# Peripherals.net
KiCad netlist of a schematic drawn in Altium Designer
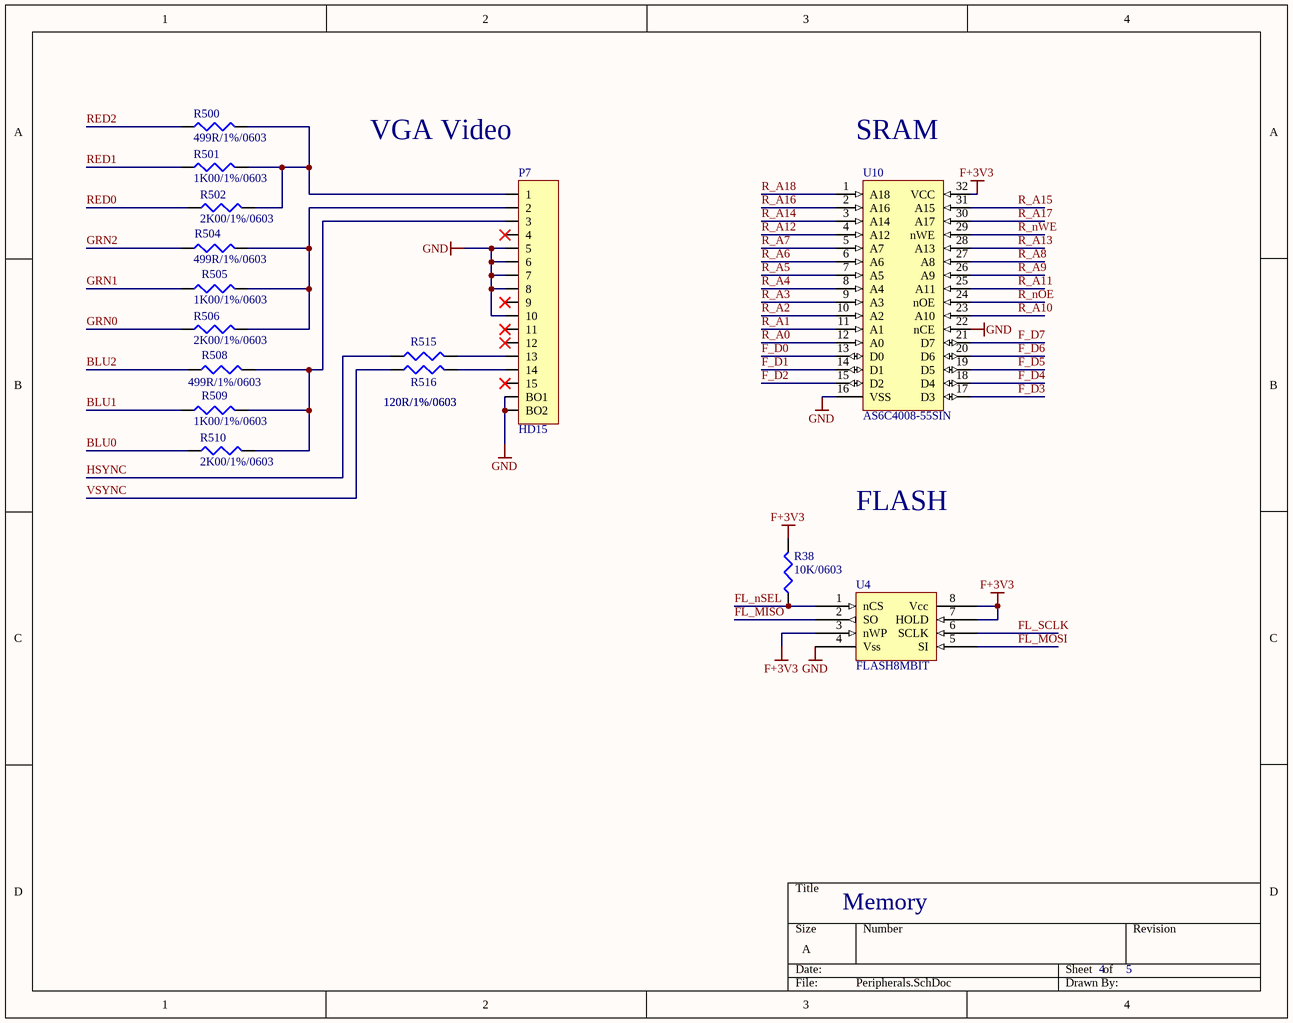
[diagram p0: Peripherals.SchDoc]

(export (version "E")
  (design (tool "Eeschema 10.0.6"))
  (components
    (comp (ref "P7")
      (value "HD15")
      (footprint "DB15FLC")
      (description "CONN DSUB HD RCPT 15POS R/A SLDR")
      (libsource (lib "C64Interface") (part "HD15"))
    )
    (comp (ref "R38")
      (value "10K/0603")
      (footprint "0603")
      (description "RES 10.0K OHM 1/10W 1% 0603 SMD")
      (fields (field (name "MFG") "Dale/Vishay"))
      (libsource (lib "C64Interface") (part "10K/0603"))
    )
    (comp (ref "R500")
      (value "499R/1%/0603")
      (footprint "0603")
      (description "499 Ohms ±1% 0.1W, 1/10W Chip Resistor 0603 (1608 Metric) Moisture Resistant Thick Film")
      (fields (field (name "MFG") "Yeago"))
      (libsource (lib "Resistors") (part "499R/1%/0603"))
    )
    (comp (ref "R501")
      (value "1K00/1%/0603")
      (footprint "0603")
      (description "1 kOhms ±1% 0.1W, 1/10W Chip Resistor 0603 (1608 Metric) Moisture Resistant Thick Film")
      (fields (field (name "MFG") "Yeago"))
      (libsource (lib "Resistors") (part "1K00/1%/0603"))
    )
    (comp (ref "R502")
      (value "2K00/1%/0603")
      (footprint "0603")
      (description "2 kOhms ±1% 0.1W, 1/10W Chip Resistor 0603 (1608 Metric) Moisture Resistant Thick Film")
      (fields (field (name "MFG") "Yeago"))
      (libsource (lib "Resistors") (part "2K00/1%/0603"))
    )
    (comp (ref "R504")
      (value "499R/1%/0603")
      (footprint "0603")
      (description "499 Ohms ±1% 0.1W, 1/10W Chip Resistor 0603 (1608 Metric) Moisture Resistant Thick Film")
      (fields (field (name "MFG") "Yeago"))
      (libsource (lib "Resistors") (part "499R/1%/0603"))
    )
    (comp (ref "R505")
      (value "1K00/1%/0603")
      (footprint "0603")
      (description "1 kOhms ±1% 0.1W, 1/10W Chip Resistor 0603 (1608 Metric) Moisture Resistant Thick Film")
      (fields (field (name "MFG") "Yeago"))
      (libsource (lib "Resistors") (part "1K00/1%/0603"))
    )
    (comp (ref "R506")
      (value "2K00/1%/0603")
      (footprint "0603")
      (description "2 kOhms ±1% 0.1W, 1/10W Chip Resistor 0603 (1608 Metric) Moisture Resistant Thick Film")
      (fields (field (name "MFG") "Yeago"))
      (libsource (lib "Resistors") (part "2K00/1%/0603"))
    )
    (comp (ref "R508")
      (value "499R/1%/0603")
      (footprint "0603")
      (description "499 Ohms ±1% 0.1W, 1/10W Chip Resistor 0603 (1608 Metric) Moisture Resistant Thick Film")
      (fields (field (name "MFG") "Yeago"))
      (libsource (lib "Resistors") (part "499R/1%/0603"))
    )
    (comp (ref "R509")
      (value "1K00/1%/0603")
      (footprint "0603")
      (description "1 kOhms ±1% 0.1W, 1/10W Chip Resistor 0603 (1608 Metric) Moisture Resistant Thick Film")
      (fields (field (name "MFG") "Yeago"))
      (libsource (lib "Resistors") (part "1K00/1%/0603"))
    )
    (comp (ref "R510")
      (value "2K00/1%/0603")
      (footprint "0603")
      (description "2 kOhms ±1% 0.1W, 1/10W Chip Resistor 0603 (1608 Metric) Moisture Resistant Thick Film")
      (fields (field (name "MFG") "Yeago"))
      (libsource (lib "Resistors") (part "2K00/1%/0603"))
    )
    (comp (ref "R515")
      (value "120R/1%/0603")
      (footprint "0603")
      (description "120 Ohms ±1% 0.1W, 1/10W Chip Resistor 0603 (1608 Metric) Moisture Resistant Thick Film")
      (fields (field (name "MFG") "Yaego"))
      (libsource (lib "C64Interface") (part "120R/1%/0603"))
    )
    (comp (ref "R516")
      (value "120R/1%/0603")
      (footprint "0603")
      (description "120 Ohms ±1% 0.1W, 1/10W Chip Resistor 0603 (1608 Metric) Moisture Resistant Thick Film")
      (fields (field (name "MFG") "Yaego"))
      (libsource (lib "C64Interface") (part "120R/1%/0603"))
    )
    (comp (ref "U4")
      (value "FLASH8MBIT")
      (footprint "SO-8WM")
      (description "IC FLASH 8MBIT SPI/QUAD 8SOIC")
      (fields (field (name "MFG") "Cyoress"))
      (libsource (lib "DigitalIC") (part "FLASH8MBIT"))
    )
    (comp (ref "U10")
      (value "AS6C4008-55SIN")
      (footprint "SOP32W")
      (description "SRAM - Asynchronous Memory IC 4Mb (512K x 8) Parallel 55 ns 32-SOP")
      (fields (field (name "MFG") "Alliance Memory, Inc."))
      (libsource (lib "DigitalIC") (part "AS6C4008-55SIN"))
    )
  )
  (nets
    (net (code "1") (name "/BLU0") (class "Default") (node (ref "R510") (pin "1") (pintype "passive")))
    (net (code "2") (name "/BLU1") (class "Default") (node (ref "R509") (pin "1") (pintype "passive")))
    (net (code "3") (name "/BLU2") (class "Default") (node (ref "R508") (pin "1") (pintype "passive")))
    (net (code "4") (name "/FL_MISO") (class "Default")
      (node (ref "U4") (pin "2") (pinfunction "SO_2") (pintype "output"))
    )
    (net (code "5") (name "/FL_MOSI") (class "Default")
      (node (ref "U4") (pin "5") (pinfunction "SI_5") (pintype "input"))
    )
    (net (code "6") (name "/FL_SCLK") (class "Default")
      (node (ref "U4") (pin "6") (pinfunction "SCLK_6") (pintype "input"))
    )
    (net (code "7") (name "/FL_nSEL") (class "Default")
      (node (ref "R38") (pin "1") (pintype "passive"))
      (node (ref "U4") (pin "1") (pinfunction "nCS_1") (pintype "input"))
    )
    (net (code "8") (name "/F_D0") (class "Default")
      (node (ref "U10") (pin "13") (pinfunction "D0_13") (pintype "bidirectional"))
    )
    (net (code "9") (name "/F_D1") (class "Default")
      (node (ref "U10") (pin "14") (pinfunction "D1_14") (pintype "bidirectional"))
    )
    (net (code "10") (name "/F_D2") (class "Default")
      (node (ref "U10") (pin "15") (pinfunction "D2_15") (pintype "bidirectional"))
    )
    (net (code "11") (name "/F_D3") (class "Default")
      (node (ref "U10") (pin "17") (pinfunction "D3_17") (pintype "bidirectional"))
    )
    (net (code "12") (name "/F_D4") (class "Default")
      (node (ref "U10") (pin "18") (pinfunction "D4_18") (pintype "bidirectional"))
    )
    (net (code "13") (name "/F_D5") (class "Default")
      (node (ref "U10") (pin "19") (pinfunction "D5_19") (pintype "bidirectional"))
    )
    (net (code "14") (name "/F_D6") (class "Default")
      (node (ref "U10") (pin "20") (pinfunction "D6_20") (pintype "bidirectional"))
    )
    (net (code "15") (name "/F_D7") (class "Default")
      (node (ref "U10") (pin "21") (pinfunction "D7_21") (pintype "bidirectional"))
    )
    (net (code "16") (name "/GRN0") (class "Default") (node (ref "R506") (pin "1") (pintype "passive")))
    (net (code "17") (name "/GRN1") (class "Default") (node (ref "R505") (pin "1") (pintype "passive")))
    (net (code "18") (name "/GRN2") (class "Default") (node (ref "R504") (pin "1") (pintype "passive")))
    (net (code "19") (name "/HSYNC") (class "Default") (node (ref "R515") (pin "1") (pintype "passive")))
    (net (code "20") (name "/RED0") (class "Default") (node (ref "R502") (pin "1") (pintype "passive")))
    (net (code "21") (name "/RED1") (class "Default") (node (ref "R501") (pin "1") (pintype "passive")))
    (net (code "22") (name "/RED2") (class "Default") (node (ref "R500") (pin "1") (pintype "passive")))
    (net (code "23") (name "/R_A0") (class "Default")
      (node (ref "U10") (pin "12") (pinfunction "A0_12") (pintype "input"))
    )
    (net (code "24") (name "/R_A1") (class "Default")
      (node (ref "U10") (pin "11") (pinfunction "A1_11") (pintype "input"))
    )
    (net (code "25") (name "/R_A2") (class "Default")
      (node (ref "U10") (pin "10") (pinfunction "A2_10") (pintype "input"))
    )
    (net (code "26") (name "/R_A3") (class "Default")
      (node (ref "U10") (pin "9") (pinfunction "A3_9") (pintype "input"))
    )
    (net (code "27") (name "/R_A4") (class "Default")
      (node (ref "U10") (pin "8") (pinfunction "A4_8") (pintype "input"))
    )
    (net (code "28") (name "/R_A5") (class "Default")
      (node (ref "U10") (pin "7") (pinfunction "A5_7") (pintype "input"))
    )
    (net (code "29") (name "/R_A6") (class "Default")
      (node (ref "U10") (pin "6") (pinfunction "A6_6") (pintype "input"))
    )
    (net (code "30") (name "/R_A7") (class "Default")
      (node (ref "U10") (pin "5") (pinfunction "A7_5") (pintype "input"))
    )
    (net (code "31") (name "/R_A8") (class "Default")
      (node (ref "U10") (pin "27") (pinfunction "A8_27") (pintype "input"))
    )
    (net (code "32") (name "/R_A9") (class "Default")
      (node (ref "U10") (pin "26") (pinfunction "A9_26") (pintype "input"))
    )
    (net (code "33") (name "/R_A10") (class "Default")
      (node (ref "U10") (pin "23") (pinfunction "A10_23") (pintype "input"))
    )
    (net (code "34") (name "/R_A11") (class "Default")
      (node (ref "U10") (pin "25") (pinfunction "A11_25") (pintype "input"))
    )
    (net (code "35") (name "/R_A12") (class "Default")
      (node (ref "U10") (pin "4") (pinfunction "A12_4") (pintype "input"))
    )
    (net (code "36") (name "/R_A13") (class "Default")
      (node (ref "U10") (pin "28") (pinfunction "A13_28") (pintype "input"))
    )
    (net (code "37") (name "/R_A14") (class "Default")
      (node (ref "U10") (pin "3") (pinfunction "A14_3") (pintype "input"))
    )
    (net (code "38") (name "/R_A15") (class "Default")
      (node (ref "U10") (pin "31") (pinfunction "A15_31") (pintype "input"))
    )
    (net (code "39") (name "/R_A16") (class "Default")
      (node (ref "U10") (pin "2") (pinfunction "A16_2") (pintype "input"))
    )
    (net (code "40") (name "/R_A17") (class "Default")
      (node (ref "U10") (pin "30") (pinfunction "A17_30") (pintype "input"))
    )
    (net (code "41") (name "/R_A18") (class "Default")
      (node (ref "U10") (pin "1") (pinfunction "A18_1") (pintype "input"))
    )
    (net (code "42") (name "/R_nOE") (class "Default")
      (node (ref "U10") (pin "24") (pinfunction "nOE_24") (pintype "input"))
    )
    (net (code "43") (name "/R_nWE") (class "Default")
      (node (ref "U10") (pin "29") (pinfunction "nWE_29") (pintype "input"))
    )
    (net (code "44") (name "/VSYNC") (class "Default") (node (ref "R516") (pin "1") (pintype "passive")))
    (net (code "45") (name "F+3V3") (class "Default")
      (node (ref "R38") (pin "2") (pintype "passive"))
      (node (ref "U10") (pin "32") (pinfunction "VCC_32") (pintype "input"))
      (node (ref "U4") (pin "3") (pinfunction "nWP_3") (pintype "input"))
      (node (ref "U4") (pin "7") (pinfunction "HOLD_7") (pintype "input"))
      (node (ref "U4") (pin "8") (pinfunction "Vcc_8") (pintype "power_in"))
    )
    (net (code "46") (name "GND") (class "Default")
      (node (ref "P7") (pin "10") (pinfunction "10_10") (pintype "passive"))
      (node (ref "P7") (pin "5") (pinfunction "5_5") (pintype "passive"))
      (node (ref "P7") (pin "6") (pinfunction "6_6") (pintype "passive"))
      (node (ref "P7") (pin "7") (pinfunction "7_7") (pintype "passive"))
      (node (ref "P7") (pin "8") (pinfunction "8_8") (pintype "passive"))
      (node (ref "P7") (pin "BO1") (pinfunction "BO1_BO1") (pintype "passive"))
      (node (ref "P7") (pin "BO2") (pinfunction "BO2_BO2") (pintype "passive"))
      (node (ref "U10") (pin "16") (pinfunction "VSS_16") (pintype "power_in"))
      (node (ref "U10") (pin "22") (pinfunction "nCE_22") (pintype "input"))
      (node (ref "U4") (pin "4") (pinfunction "Vss_4") (pintype "power_in"))
    )
    (net (code "47") (name "Net-(P7-Pad1)") (class "Default")
      (node (ref "P7") (pin "1") (pinfunction "1_1") (pintype "passive"))
      (node (ref "R500") (pin "2") (pintype "passive"))
      (node (ref "R501") (pin "2") (pintype "passive"))
      (node (ref "R502") (pin "2") (pintype "passive"))
    )
    (net (code "48") (name "Net-(P7-Pad2)") (class "Default")
      (node (ref "P7") (pin "2") (pinfunction "2_2") (pintype "passive"))
      (node (ref "R504") (pin "2") (pintype "passive"))
      (node (ref "R505") (pin "2") (pintype "passive"))
      (node (ref "R506") (pin "2") (pintype "passive"))
    )
    (net (code "49") (name "Net-(P7-Pad3)") (class "Default")
      (node (ref "P7") (pin "3") (pinfunction "3_3") (pintype "passive"))
      (node (ref "R508") (pin "2") (pintype "passive"))
      (node (ref "R509") (pin "2") (pintype "passive"))
      (node (ref "R510") (pin "2") (pintype "passive"))
    )
    (net (code "50") (name "Net-(P7-Pad13)") (class "Default")
      (node (ref "P7") (pin "13") (pinfunction "13_13") (pintype "passive"))
      (node (ref "R515") (pin "2") (pintype "passive"))
    )
    (net (code "51") (name "Net-(P7-Pad14)") (class "Default")
      (node (ref "P7") (pin "14") (pinfunction "14_14") (pintype "passive"))
      (node (ref "R516") (pin "2") (pintype "passive"))
    )
    (net (code "52") (name "unconnected-(P7-Pad4)") (class "Default")
      (node (ref "P7") (pin "4") (pinfunction "4_4") (pintype "passive+no_connect"))
    )
    (net (code "53") (name "unconnected-(P7-Pad9)") (class "Default")
      (node (ref "P7") (pin "9") (pinfunction "9_9") (pintype "passive+no_connect"))
    )
    (net (code "54") (name "unconnected-(P7-Pad11)") (class "Default")
      (node (ref "P7") (pin "11") (pinfunction "11_11") (pintype "passive+no_connect"))
    )
    (net (code "55") (name "unconnected-(P7-Pad12)") (class "Default")
      (node (ref "P7") (pin "12") (pinfunction "12_12") (pintype "passive+no_connect"))
    )
    (net (code "56") (name "unconnected-(P7-Pad15)") (class "Default")
      (node (ref "P7") (pin "15") (pinfunction "15_15") (pintype "passive+no_connect"))
    )
  )
)
